# ESP32.net
KiCad netlist of a schematic drawn in Altium Designer
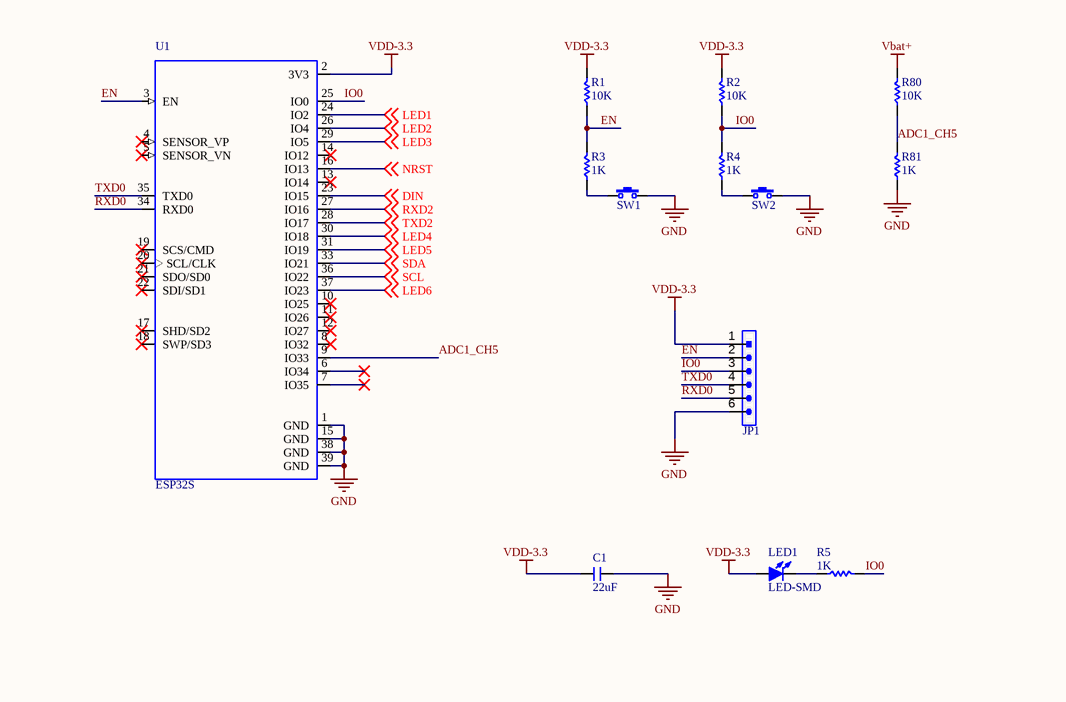
[diagram p0: ESP32.SchDoc]

(export (version "E")
  (design (tool "Eeschema 10.0.6"))
  (components
    (comp (ref "C1")
      (value "22uF")
      (footprint "C 0805")
      (description "Non-polar patch capacitor")
      (fields (field (name "版权归属") "源创客"))
      (libsource (lib "Passive (Resistor-Capacitor-Inductor-Veristor-Ferrite)") (part "C"))
    )
    (comp (ref "JP1")
      (value "HDR-1X6")
      (footprint "HDR-1X6")
      (description "6P Connector")
      (fields (field (name "版权归属") "源创客"))
      (libsource (lib "Connectors") (part "Header 6"))
    )
    (comp (ref "LED1")
      (value "LED-SMD")
      (footprint "LED 0805B")
      (description "Patch LED")
      (fields (field (name "版权归属") "源创客"))
      (libsource (lib "LED") (part "LED-SMD"))
    )
    (comp (ref "R1")
      (value "10K")
      (footprint "R 0805")
      (description "Chip resistor")
      (fields (field (name "版权归属") "源创客"))
      (libsource (lib "Passive (Resistor-Capacitor-Inductor-Veristor-Ferrite)") (part "R"))
    )
    (comp (ref "R2")
      (value "10K")
      (footprint "R 0805")
      (description "Chip resistor")
      (fields (field (name "版权归属") "源创客"))
      (libsource (lib "Passive (Resistor-Capacitor-Inductor-Veristor-Ferrite)") (part "R"))
    )
    (comp (ref "R3")
      (value "1K")
      (footprint "R 0805")
      (description "Chip resistor")
      (fields (field (name "版权归属") "源创客"))
      (libsource (lib "Passive (Resistor-Capacitor-Inductor-Veristor-Ferrite)") (part "R"))
    )
    (comp (ref "R4")
      (value "1K")
      (footprint "R 0805")
      (description "Chip resistor")
      (fields (field (name "版权归属") "源创客"))
      (libsource (lib "Passive (Resistor-Capacitor-Inductor-Veristor-Ferrite)") (part "R"))
    )
    (comp (ref "R5")
      (value "1K")
      (footprint "R 0805")
      (description "Chip resistor")
      (fields (field (name "版权归属") "源创客"))
      (libsource (lib "Passive (Resistor-Capacitor-Inductor-Veristor-Ferrite)") (part "R"))
    )
    (comp (ref "R80")
      (value "10K")
      (footprint "R 0805")
      (description "Chip resistor")
      (fields (field (name "版权归属") "源创客"))
      (libsource (lib "Passive (Resistor-Capacitor-Inductor-Veristor-Ferrite)") (part "R"))
    )
    (comp (ref "R81")
      (value "1K")
      (footprint "R 0805")
      (description "Chip resistor")
      (fields (field (name "版权归属") "源创客"))
      (libsource (lib "Passive (Resistor-Capacitor-Inductor-Veristor-Ferrite)") (part "R"))
    )
    (comp (ref "SW1")
      (value "3x6x5")
      (footprint "TSW SMD-3*6*2.5")
      (description "3x6 tact switch")
      (fields (field (name "版权归属") "源创客"))
      (libsource (lib "Button") (part "TSW 3x6"))
    )
    (comp (ref "SW2")
      (value "3x6x5")
      (footprint "TSW SMD-3*6*2.5")
      (description "3x6 tact switch")
      (fields (field (name "版权归属") "源创客"))
      (libsource (lib "Button") (part "TSW 3x6"))
    )
    (comp (ref "U1")
      (value "ESP32S")
      (footprint "ESP32S")
      (fields (field (name "MP") "ESP32-WROOM-32D") (field (name "MF") "Espressif Systems"))
      (libsource (lib "Espressif") (part "ESP32S"))
    )
  )
  (nets
    (net (code "1") (name "/ADC1_CH5") (class "Default")
      (node (ref "R80") (pin "1") (pinfunction "1_1") (pintype "passive"))
      (node (ref "R81") (pin "2") (pinfunction "2_2") (pintype "passive"))
      (node (ref "U1") (pin "9") (pinfunction "IO33_9") (pintype "bidirectional"))
    )
    (net (code "2") (name "/EN") (class "Default")
      (node (ref "JP1") (pin "2") (pintype "passive"))
      (node (ref "R1") (pin "1") (pinfunction "1_1") (pintype "passive"))
      (node (ref "R3") (pin "2") (pinfunction "2_2") (pintype "passive"))
      (node (ref "U1") (pin "3") (pinfunction "EN_3") (pintype "input"))
    )
    (net (code "3") (name "/IO0") (class "Default")
      (node (ref "JP1") (pin "3") (pintype "passive"))
      (node (ref "R2") (pin "1") (pinfunction "1_1") (pintype "passive"))
      (node (ref "R4") (pin "2") (pinfunction "2_2") (pintype "passive"))
      (node (ref "R5") (pin "2") (pinfunction "2_2") (pintype "passive"))
      (node (ref "U1") (pin "25") (pinfunction "IO0_25") (pintype "bidirectional"))
    )
    (net (code "4") (name "/RXD0") (class "Default")
      (node (ref "JP1") (pin "5") (pintype "passive"))
      (node (ref "U1") (pin "34") (pinfunction "RXD0_34") (pintype "bidirectional"))
    )
    (net (code "5") (name "/TXD0") (class "Default")
      (node (ref "JP1") (pin "4") (pintype "passive"))
      (node (ref "U1") (pin "35") (pinfunction "TXD0_35") (pintype "bidirectional"))
    )
    (net (code "6") (name "DIN") (class "Default")
      (node (ref "U1") (pin "23") (pinfunction "IO15_23") (pintype "bidirectional"))
    )
    (net (code "7") (name "GND") (class "Default")
      (node (ref "C1") (pin "2") (pinfunction "2_2") (pintype "passive"))
      (node (ref "JP1") (pin "6") (pintype "passive"))
      (node (ref "R81") (pin "1") (pinfunction "1_1") (pintype "passive"))
      (node (ref "SW1") (pin "2") (pinfunction "2_2") (pintype "passive"))
      (node (ref "SW2") (pin "2") (pinfunction "2_2") (pintype "passive"))
      (node (ref "U1") (pin "1") (pinfunction "GND_1") (pintype "power_in"))
      (node (ref "U1") (pin "15") (pinfunction "GND_15") (pintype "power_in"))
      (node (ref "U1") (pin "38") (pinfunction "GND_38") (pintype "power_in"))
      (node (ref "U1") (pin "39") (pinfunction "GND_39") (pintype "power_in"))
    )
    (net (code "8") (name "LED1") (class "Default")
      (node (ref "U1") (pin "24") (pinfunction "IO2_24") (pintype "bidirectional"))
    )
    (net (code "9") (name "LED2") (class "Default")
      (node (ref "U1") (pin "26") (pinfunction "IO4_26") (pintype "bidirectional"))
    )
    (net (code "10") (name "LED3") (class "Default")
      (node (ref "U1") (pin "29") (pinfunction "IO5_29") (pintype "bidirectional"))
    )
    (net (code "11") (name "LED4") (class "Default")
      (node (ref "U1") (pin "30") (pinfunction "IO18_30") (pintype "bidirectional"))
    )
    (net (code "12") (name "LED5") (class "Default")
      (node (ref "U1") (pin "31") (pinfunction "IO19_31") (pintype "bidirectional"))
    )
    (net (code "13") (name "LED6") (class "Default")
      (node (ref "U1") (pin "37") (pinfunction "IO23_37") (pintype "bidirectional"))
    )
    (net (code "14") (name "NRST") (class "Default")
      (node (ref "U1") (pin "16") (pinfunction "IO13_16") (pintype "bidirectional"))
    )
    (net (code "15") (name "Net-(LED1-K)") (class "Default")
      (node (ref "LED1") (pin "2") (pinfunction "K_2") (pintype "passive"))
      (node (ref "R5") (pin "1") (pinfunction "1_1") (pintype "passive"))
    )
    (net (code "16") (name "Net-(R3-Pad1)") (class "Default")
      (node (ref "R3") (pin "1") (pinfunction "1_1") (pintype "passive"))
      (node (ref "SW1") (pin "1") (pinfunction "1_1") (pintype "passive"))
    )
    (net (code "17") (name "Net-(R4-Pad1)") (class "Default")
      (node (ref "R4") (pin "1") (pinfunction "1_1") (pintype "passive"))
      (node (ref "SW2") (pin "1") (pinfunction "1_1") (pintype "passive"))
    )
    (net (code "18") (name "RXD2") (class "Default")
      (node (ref "U1") (pin "27") (pinfunction "IO16_27") (pintype "bidirectional"))
    )
    (net (code "19") (name "SCL") (class "Default")
      (node (ref "U1") (pin "36") (pinfunction "IO22_36") (pintype "bidirectional"))
    )
    (net (code "20") (name "SDA") (class "Default")
      (node (ref "U1") (pin "33") (pinfunction "IO21_33") (pintype "bidirectional"))
    )
    (net (code "21") (name "TXD2") (class "Default")
      (node (ref "U1") (pin "28") (pinfunction "IO17_28") (pintype "bidirectional"))
    )
    (net (code "22") (name "VDD-3.3") (class "Default")
      (node (ref "C1") (pin "1") (pinfunction "1_1") (pintype "passive"))
      (node (ref "JP1") (pin "1") (pintype "passive"))
      (node (ref "LED1") (pin "1") (pinfunction "A_1") (pintype "passive"))
      (node (ref "R1") (pin "2") (pinfunction "2_2") (pintype "passive"))
      (node (ref "R2") (pin "2") (pinfunction "2_2") (pintype "passive"))
      (node (ref "U1") (pin "2") (pinfunction "3V3_2") (pintype "power_in"))
    )
    (net (code "23") (name "Vbat+") (class "Default")
      (node (ref "R80") (pin "2") (pinfunction "2_2") (pintype "passive"))
    )
    (net (code "24") (name "unconnected-(U1-IO12-Pad14)") (class "Default")
      (node (ref "U1") (pin "14") (pinfunction "IO12_14") (pintype "bidirectional+no_connect"))
    )
    (net (code "25") (name "unconnected-(U1-IO14-Pad13)") (class "Default")
      (node (ref "U1") (pin "13") (pinfunction "IO14_13") (pintype "bidirectional+no_connect"))
    )
    (net (code "26") (name "unconnected-(U1-IO25-Pad10)") (class "Default")
      (node (ref "U1") (pin "10") (pinfunction "IO25_10") (pintype "bidirectional+no_connect"))
    )
    (net (code "27") (name "unconnected-(U1-IO26-Pad11)") (class "Default")
      (node (ref "U1") (pin "11") (pinfunction "IO26_11") (pintype "bidirectional+no_connect"))
    )
    (net (code "28") (name "unconnected-(U1-IO27-Pad12)") (class "Default")
      (node (ref "U1") (pin "12") (pinfunction "IO27_12") (pintype "bidirectional+no_connect"))
    )
    (net (code "29") (name "unconnected-(U1-IO32-Pad8)") (class "Default")
      (node (ref "U1") (pin "8") (pinfunction "IO32_8") (pintype "bidirectional+no_connect"))
    )
    (net (code "30") (name "unconnected-(U1-IO34-Pad6)") (class "Default")
      (node (ref "U1") (pin "6") (pinfunction "IO34_6") (pintype "bidirectional+no_connect"))
    )
    (net (code "31") (name "unconnected-(U1-IO35-Pad7)") (class "Default")
      (node (ref "U1") (pin "7") (pinfunction "IO35_7") (pintype "bidirectional+no_connect"))
    )
    (net (code "32") (name "unconnected-(U1-SCL{slash}CLK-Pad20)") (class "Default")
      (node (ref "U1") (pin "20") (pinfunction "SCL/CLK_20") (pintype "bidirectional+no_connect"))
    )
    (net (code "33") (name "unconnected-(U1-SCS{slash}CMD-Pad19)") (class "Default")
      (node (ref "U1") (pin "19") (pinfunction "SCS/CMD_19") (pintype "bidirectional+no_connect"))
    )
    (net (code "34") (name "unconnected-(U1-SDI{slash}SD1-Pad22)") (class "Default")
      (node (ref "U1") (pin "22") (pinfunction "SDI/SD1_22") (pintype "bidirectional+no_connect"))
    )
    (net (code "35") (name "unconnected-(U1-SDO{slash}SD0-Pad21)") (class "Default")
      (node (ref "U1") (pin "21") (pinfunction "SDO/SD0_21") (pintype "bidirectional+no_connect"))
    )
    (net (code "36") (name "unconnected-(U1-SENSOR_VN-Pad5)") (class "Default")
      (node (ref "U1") (pin "5") (pinfunction "SENSOR_VN_5") (pintype "input+no_connect"))
    )
    (net (code "37") (name "unconnected-(U1-SENSOR_VP-Pad4)") (class "Default")
      (node (ref "U1") (pin "4") (pinfunction "SENSOR_VP_4") (pintype "input+no_connect"))
    )
    (net (code "38") (name "unconnected-(U1-SHD{slash}SD2-Pad17)") (class "Default")
      (node (ref "U1") (pin "17") (pinfunction "SHD/SD2_17") (pintype "bidirectional+no_connect"))
    )
    (net (code "39") (name "unconnected-(U1-SWP{slash}SD3-Pad18)") (class "Default")
      (node (ref "U1") (pin "18") (pinfunction "SWP/SD3_18") (pintype "bidirectional+no_connect"))
    )
  )
)
